# booz_imu_xz.net
KiCad netlist of a schematic drawn in EAGLE
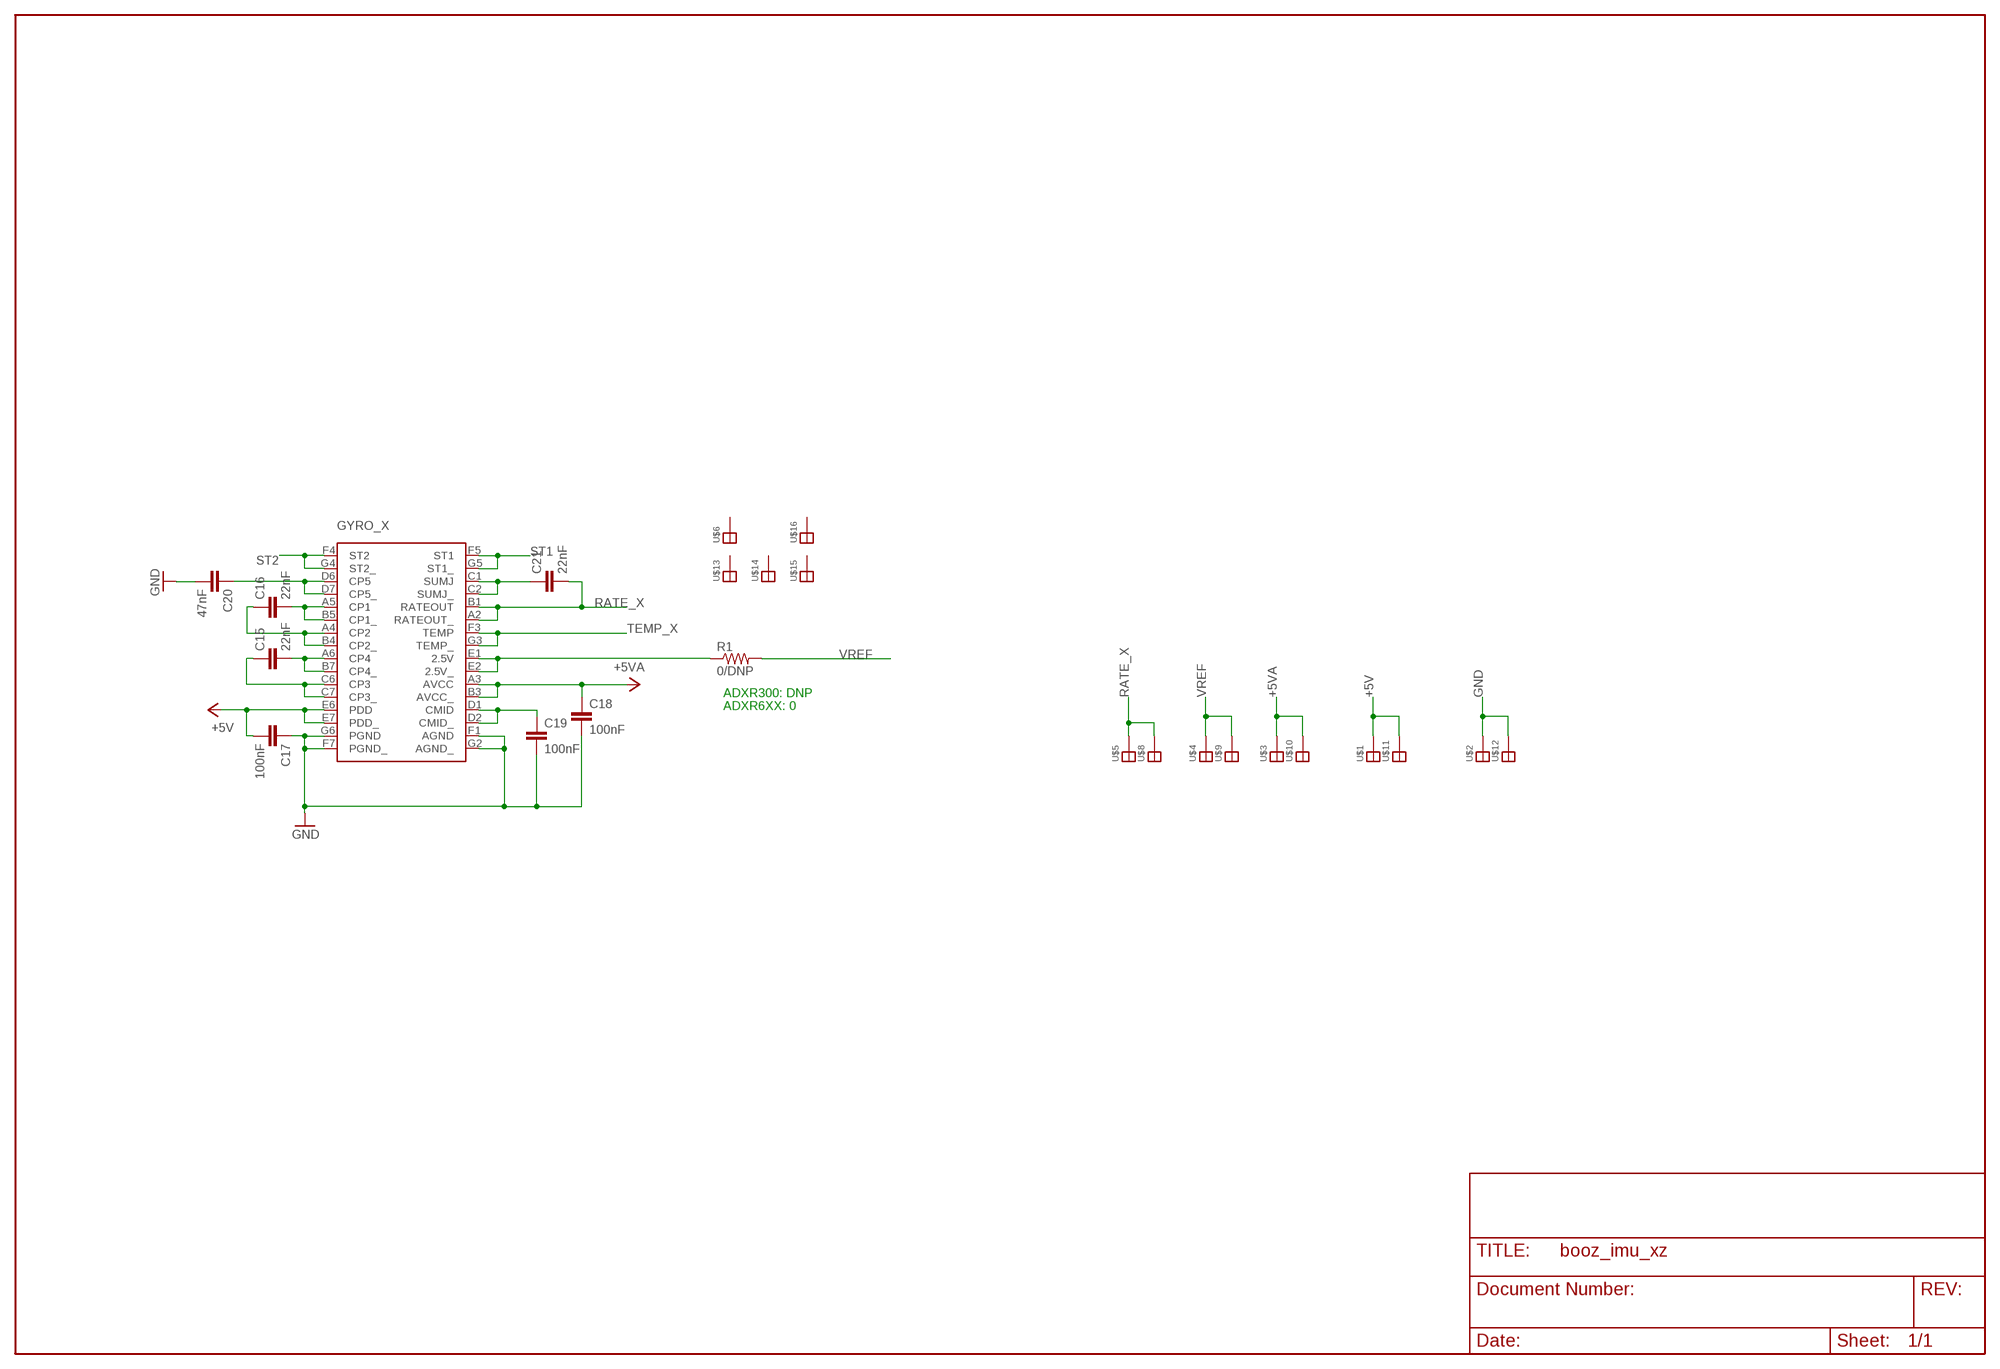
[diagram p0: schematic, sheet 1]

(export (version "E")
  (design (tool "Eeschema 10.0.6"))
  (components
    (comp (ref "C15")
      (value "22nF")
      (footprint "eagle-import:C0603K")
      (libsource (lib "eagle-import") (part "C-EUC0603K"))
    )
    (comp (ref "C16")
      (value "22nF")
      (footprint "eagle-import:C0603K")
      (libsource (lib "eagle-import") (part "C-EUC0603K"))
    )
    (comp (ref "C17")
      (value "100nF")
      (footprint "eagle-import:C0603K")
      (libsource (lib "eagle-import") (part "C-EUC0603K"))
    )
    (comp (ref "C18")
      (value "100nF")
      (footprint "eagle-import:C0603K")
      (libsource (lib "eagle-import") (part "C-EUC0603K"))
    )
    (comp (ref "C19")
      (value "100nF")
      (footprint "eagle-import:C0603K")
      (libsource (lib "eagle-import") (part "C-EUC0603K"))
    )
    (comp (ref "C20")
      (value "47nF")
      (footprint "eagle-import:C0603K")
      (libsource (lib "eagle-import") (part "C-EUC0603K"))
    )
    (comp (ref "C21")
      (value "22nF")
      (footprint "eagle-import:C0603K")
      (libsource (lib "eagle-import") (part "C-EUC0603K"))
    )
    (comp (ref "GYRO_X")
      (value "ADXR")
      (footprint "eagle-import:BC-32")
      (libsource (lib "eagle-import") (part "ADXR"))
    )
    (comp (ref "R1")
      (value "0/DNP")
      (footprint "eagle-import:R0603")
      (libsource (lib "eagle-import") (part "R-US_R0603"))
    )
    (comp (ref "U$1")
      (value "SOLDER_PAD")
      (footprint "eagle-import:SOLDER_PAD")
      (libsource (lib "eagle-import") (part "SOLDER_PAD"))
    )
    (comp (ref "U$2")
      (value "SOLDER_PAD")
      (footprint "eagle-import:SOLDER_PAD")
      (libsource (lib "eagle-import") (part "SOLDER_PAD"))
    )
    (comp (ref "U$3")
      (value "SOLDER_PAD")
      (footprint "eagle-import:SOLDER_PAD")
      (libsource (lib "eagle-import") (part "SOLDER_PAD"))
    )
    (comp (ref "U$4")
      (value "SOLDER_PAD")
      (footprint "eagle-import:SOLDER_PAD")
      (libsource (lib "eagle-import") (part "SOLDER_PAD"))
    )
    (comp (ref "U$5")
      (value "SOLDER_PAD")
      (footprint "eagle-import:SOLDER_PAD")
      (libsource (lib "eagle-import") (part "SOLDER_PAD"))
    )
    (comp (ref "U$6")
      (value "SOLDER_PAD")
      (footprint "eagle-import:SOLDER_PAD")
      (libsource (lib "eagle-import") (part "SOLDER_PAD"))
    )
    (comp (ref "U$8")
      (value "SOLDER_PAD")
      (footprint "eagle-import:SOLDER_PAD")
      (libsource (lib "eagle-import") (part "SOLDER_PAD"))
    )
    (comp (ref "U$9")
      (value "SOLDER_PAD")
      (footprint "eagle-import:SOLDER_PAD")
      (libsource (lib "eagle-import") (part "SOLDER_PAD"))
    )
    (comp (ref "U$10")
      (value "SOLDER_PAD")
      (footprint "eagle-import:SOLDER_PAD")
      (libsource (lib "eagle-import") (part "SOLDER_PAD"))
    )
    (comp (ref "U$11")
      (value "SOLDER_PAD")
      (footprint "eagle-import:SOLDER_PAD")
      (libsource (lib "eagle-import") (part "SOLDER_PAD"))
    )
    (comp (ref "U$12")
      (value "SOLDER_PAD")
      (footprint "eagle-import:SOLDER_PAD")
      (libsource (lib "eagle-import") (part "SOLDER_PAD"))
    )
    (comp (ref "U$13")
      (value "SOLDER_PAD")
      (footprint "eagle-import:SOLDER_PAD")
      (libsource (lib "eagle-import") (part "SOLDER_PAD"))
    )
    (comp (ref "U$14")
      (value "SOLDER_PAD")
      (footprint "eagle-import:SOLDER_PAD")
      (libsource (lib "eagle-import") (part "SOLDER_PAD"))
    )
    (comp (ref "U$15")
      (value "SOLDER_PAD")
      (footprint "eagle-import:SOLDER_PAD")
      (libsource (lib "eagle-import") (part "SOLDER_PAD"))
    )
    (comp (ref "U$16")
      (value "SOLDER_PAD")
      (footprint "eagle-import:SOLDER_PAD")
      (libsource (lib "eagle-import") (part "SOLDER_PAD"))
    )
  )
  (nets
    (net (code "1") (name "+5V") (class "Default")
      (node (ref "C17") (pin "2") (pinfunction "2_2") (pintype "passive"))
      (node (ref "GYRO_X") (pin "E6") (pinfunction "PDD_E6") (pintype "bidirectional"))
      (node (ref "GYRO_X") (pin "E7") (pinfunction "PDD__E7") (pintype "bidirectional"))
      (node (ref "U$1") (pin "P$1") (pinfunction "P$1_P$1") (pintype "bidirectional"))
      (node (ref "U$11") (pin "P$1") (pinfunction "P$1_P$1") (pintype "bidirectional"))
    )
    (net (code "2") (name "+5VA") (class "Default")
      (node (ref "C18") (pin "1") (pinfunction "1_1") (pintype "passive"))
      (node (ref "GYRO_X") (pin "A3") (pinfunction "AVCC_A3") (pintype "bidirectional"))
      (node (ref "GYRO_X") (pin "B3") (pinfunction "AVCC__B3") (pintype "bidirectional"))
      (node (ref "U$10") (pin "P$1") (pinfunction "P$1_P$1") (pintype "bidirectional"))
      (node (ref "U$3") (pin "P$1") (pinfunction "P$1_P$1") (pintype "bidirectional"))
    )
    (net (code "3") (name "/RATE_X") (class "Default")
      (node (ref "C21") (pin "2") (pinfunction "2_2") (pintype "passive"))
      (node (ref "GYRO_X") (pin "A2") (pinfunction "RATEOUT__A2") (pintype "bidirectional"))
      (node (ref "GYRO_X") (pin "B1") (pinfunction "RATEOUT_B1") (pintype "bidirectional"))
      (node (ref "U$5") (pin "P$1") (pinfunction "P$1_P$1") (pintype "bidirectional"))
      (node (ref "U$8") (pin "P$1") (pinfunction "P$1_P$1") (pintype "bidirectional"))
    )
    (net (code "4") (name "/ST1") (class "Default")
      (node (ref "GYRO_X") (pin "F5") (pinfunction "ST1_F5") (pintype "bidirectional"))
      (node (ref "GYRO_X") (pin "G5") (pinfunction "ST1__G5") (pintype "bidirectional"))
    )
    (net (code "5") (name "/ST2") (class "Default")
      (node (ref "GYRO_X") (pin "F4") (pinfunction "ST2_F4") (pintype "bidirectional"))
      (node (ref "GYRO_X") (pin "G4") (pinfunction "ST2__G4") (pintype "bidirectional"))
    )
    (net (code "6") (name "/TEMP_X") (class "Default")
      (node (ref "GYRO_X") (pin "F3") (pinfunction "TEMP_F3") (pintype "bidirectional"))
      (node (ref "GYRO_X") (pin "G3") (pinfunction "TEMP__G3") (pintype "bidirectional"))
    )
    (net (code "7") (name "/VREF") (class "Default")
      (node (ref "R1") (pin "2") (pinfunction "2_2") (pintype "passive"))
      (node (ref "U$4") (pin "P$1") (pinfunction "P$1_P$1") (pintype "bidirectional"))
      (node (ref "U$9") (pin "P$1") (pinfunction "P$1_P$1") (pintype "bidirectional"))
    )
    (net (code "8") (name "GND") (class "Default")
      (node (ref "C17") (pin "1") (pinfunction "1_1") (pintype "passive"))
      (node (ref "C18") (pin "2") (pinfunction "2_2") (pintype "passive"))
      (node (ref "C19") (pin "2") (pinfunction "2_2") (pintype "passive"))
      (node (ref "C20") (pin "2") (pinfunction "2_2") (pintype "passive"))
      (node (ref "GYRO_X") (pin "F1") (pinfunction "AGND_F1") (pintype "bidirectional"))
      (node (ref "GYRO_X") (pin "F7") (pinfunction "PGND__F7") (pintype "bidirectional"))
      (node (ref "GYRO_X") (pin "G2") (pinfunction "AGND__G2") (pintype "bidirectional"))
      (node (ref "GYRO_X") (pin "G6") (pinfunction "PGND_G6") (pintype "bidirectional"))
      (node (ref "U$12") (pin "P$1") (pinfunction "P$1_P$1") (pintype "bidirectional"))
      (node (ref "U$2") (pin "P$1") (pinfunction "P$1_P$1") (pintype "bidirectional"))
    )
    (net (code "9") (name "Net-(GYRO_X-2.5V)") (class "Default")
      (node (ref "GYRO_X") (pin "E1") (pinfunction "2.5V_E1") (pintype "bidirectional"))
      (node (ref "GYRO_X") (pin "E2") (pinfunction "2.5V__E2") (pintype "bidirectional"))
      (node (ref "R1") (pin "1") (pinfunction "1_1") (pintype "passive"))
    )
    (net (code "10") (name "Net-(GYRO_X-CMID)") (class "Default")
      (node (ref "C19") (pin "1") (pinfunction "1_1") (pintype "passive"))
      (node (ref "GYRO_X") (pin "D1") (pinfunction "CMID_D1") (pintype "bidirectional"))
      (node (ref "GYRO_X") (pin "D2") (pinfunction "CMID__D2") (pintype "bidirectional"))
    )
    (net (code "11") (name "Net-(GYRO_X-CP1)") (class "Default")
      (node (ref "C16") (pin "2") (pinfunction "2_2") (pintype "passive"))
      (node (ref "GYRO_X") (pin "A5") (pinfunction "CP1_A5") (pintype "bidirectional"))
      (node (ref "GYRO_X") (pin "B5") (pinfunction "CP1__B5") (pintype "bidirectional"))
    )
    (net (code "12") (name "Net-(GYRO_X-CP2)") (class "Default")
      (node (ref "C16") (pin "1") (pinfunction "1_1") (pintype "passive"))
      (node (ref "GYRO_X") (pin "A4") (pinfunction "CP2_A4") (pintype "bidirectional"))
      (node (ref "GYRO_X") (pin "B4") (pinfunction "CP2__B4") (pintype "bidirectional"))
    )
    (net (code "13") (name "Net-(GYRO_X-CP3)") (class "Default")
      (node (ref "C15") (pin "1") (pinfunction "1_1") (pintype "passive"))
      (node (ref "GYRO_X") (pin "C6") (pinfunction "CP3_C6") (pintype "bidirectional"))
      (node (ref "GYRO_X") (pin "C7") (pinfunction "CP3__C7") (pintype "bidirectional"))
    )
    (net (code "14") (name "Net-(GYRO_X-CP4)") (class "Default")
      (node (ref "C15") (pin "2") (pinfunction "2_2") (pintype "passive"))
      (node (ref "GYRO_X") (pin "A6") (pinfunction "CP4_A6") (pintype "bidirectional"))
      (node (ref "GYRO_X") (pin "B7") (pinfunction "CP4__B7") (pintype "bidirectional"))
    )
    (net (code "15") (name "Net-(GYRO_X-CP5)") (class "Default")
      (node (ref "C20") (pin "1") (pinfunction "1_1") (pintype "passive"))
      (node (ref "GYRO_X") (pin "D6") (pinfunction "CP5_D6") (pintype "bidirectional"))
      (node (ref "GYRO_X") (pin "D7") (pinfunction "CP5__D7") (pintype "bidirectional"))
    )
    (net (code "16") (name "Net-(GYRO_X-SUMJ)") (class "Default")
      (node (ref "C21") (pin "1") (pinfunction "1_1") (pintype "passive"))
      (node (ref "GYRO_X") (pin "C1") (pinfunction "SUMJ_C1") (pintype "bidirectional"))
      (node (ref "GYRO_X") (pin "C2") (pinfunction "SUMJ__C2") (pintype "bidirectional"))
    )
    (net (code "17") (name "unconnected-(U$6-PadP$1)") (class "Default")
      (node (ref "U$6") (pin "P$1") (pinfunction "P$1_P$1") (pintype "bidirectional"))
    )
    (net (code "18") (name "unconnected-(U$13-PadP$1)") (class "Default")
      (node (ref "U$13") (pin "P$1") (pinfunction "P$1_P$1") (pintype "bidirectional"))
    )
    (net (code "19") (name "unconnected-(U$14-PadP$1)") (class "Default")
      (node (ref "U$14") (pin "P$1") (pinfunction "P$1_P$1") (pintype "bidirectional"))
    )
    (net (code "20") (name "unconnected-(U$15-PadP$1)") (class "Default")
      (node (ref "U$15") (pin "P$1") (pinfunction "P$1_P$1") (pintype "bidirectional"))
    )
    (net (code "21") (name "unconnected-(U$16-PadP$1)") (class "Default")
      (node (ref "U$16") (pin "P$1") (pinfunction "P$1_P$1") (pintype "bidirectional"))
    )
  )
)
